# ATtiny10_v2.net
KiCad netlist of a schematic drawn in EAGLE
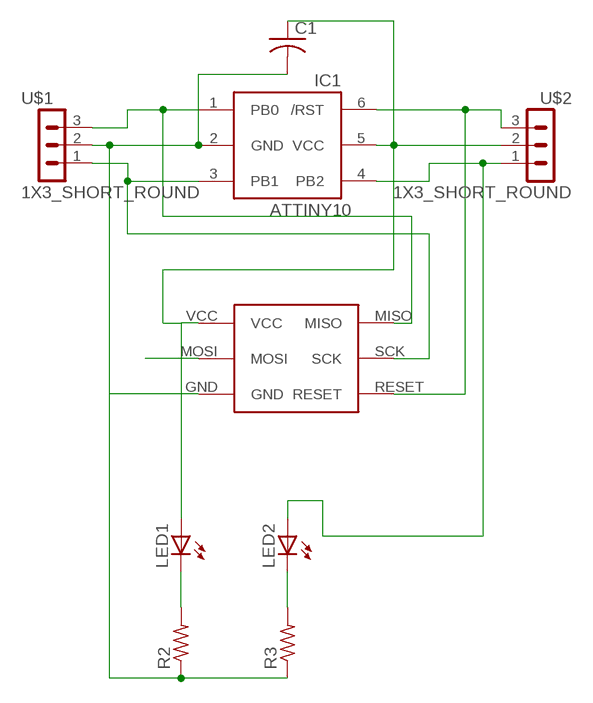
[diagram p0: schematic, sheet 1]

(export (version "E")
  (design (tool "Eeschema 10.0.6"))
  (components
    (comp (ref "C1")
      (value "C-USC0402K")
      (footprint "eagle-import:C0402K")
      (libsource (lib "eagle-import") (part "C-USC0402K"))
    )
    (comp (ref "IC1")
      (value "ATTINY10")
      (footprint "eagle-import:SOT23-6")
      (libsource (lib "eagle-import") (part "ATTINY10"))
    )
    (comp (ref "LED1")
      (value "LEDCHIPLED_0603")
      (footprint "eagle-import:CHIPLED_0603")
      (libsource (lib "eagle-import") (part "LEDCHIPLED_0603"))
    )
    (comp (ref "LED2")
      (value "LEDCHIPLED_0603")
      (footprint "eagle-import:CHIPLED_0603")
      (libsource (lib "eagle-import") (part "LEDCHIPLED_0603"))
    )
    (comp (ref "R2")
      (value "R-US_R0402")
      (footprint "eagle-import:R0402")
      (libsource (lib "eagle-import") (part "R-US_R0402"))
    )
    (comp (ref "R3")
      (value "R-US_R0402")
      (footprint "eagle-import:R0402")
      (libsource (lib "eagle-import") (part "R-US_R0402"))
    )
    (comp (ref "U$1")
      (value "1X3_SHORT_ROUND")
      (footprint "eagle-import:1X3_SHORT_ROUND")
      (libsource (lib "eagle-import") (part "1X3_SHORT_ROUND"))
    )
    (comp (ref "U$2")
      (value "1X3_SHORT_ROUND")
      (footprint "eagle-import:1X3_SHORT_ROUND")
      (libsource (lib "eagle-import") (part "1X3_SHORT_ROUND"))
    )
    (comp (ref "U$4")
      (value "TINY-AVR-POGO-PIN-KEY")
      (footprint "eagle-import:TINY-AVR-POGO-PIN-KEY")
      (libsource (lib "eagle-import") (part "TINY-AVR-POGO-PIN-KEY"))
    )
  )
  (nets
    (net (code "1") (name "Net-(IC1-GND)") (class "Default")
      (node (ref "C1") (pin "2") (pinfunction "2_2") (pintype "passive"))
      (node (ref "IC1") (pin "2") (pinfunction "GND_2") (pintype "power_in"))
      (node (ref "R2") (pin "1") (pinfunction "1_1") (pintype "passive"))
      (node (ref "R3") (pin "1") (pinfunction "1_1") (pintype "passive"))
      (node (ref "U$1") (pin "2") (pinfunction "5_2") (pintype "passive"))
      (node (ref "U$4") (pin "GND") (pinfunction "GND_GND") (pintype "bidirectional"))
    )
    (net (code "2") (name "Net-(IC1-PB0)") (class "Default")
      (node (ref "IC1") (pin "1") (pinfunction "PB0_1") (pintype "bidirectional"))
      (node (ref "U$1") (pin "3") (pinfunction "6_3") (pintype "passive"))
      (node (ref "U$4") (pin "MISO") (pinfunction "MISO_MISO") (pintype "bidirectional"))
    )
    (net (code "3") (name "Net-(IC1-PB1)") (class "Default")
      (node (ref "IC1") (pin "3") (pinfunction "PB1_3") (pintype "bidirectional"))
      (node (ref "U$1") (pin "1") (pinfunction "4_1") (pintype "passive"))
      (node (ref "U$4") (pin "SCK") (pinfunction "SCK_SCK") (pintype "bidirectional"))
    )
    (net (code "4") (name "Net-(IC1-PB2)") (class "Default")
      (node (ref "IC1") (pin "4") (pinfunction "PB2_4") (pintype "bidirectional"))
      (node (ref "LED2") (pin "A") (pinfunction "A_A") (pintype "passive"))
      (node (ref "U$2") (pin "1") (pinfunction "4_1") (pintype "passive"))
    )
    (net (code "5") (name "Net-(IC1-VCC)") (class "Default")
      (node (ref "C1") (pin "1") (pinfunction "1_1") (pintype "passive"))
      (node (ref "IC1") (pin "5") (pinfunction "VCC_5") (pintype "power_in"))
      (node (ref "LED1") (pin "A") (pinfunction "A_A") (pintype "passive"))
      (node (ref "U$2") (pin "2") (pinfunction "5_2") (pintype "passive"))
      (node (ref "U$4") (pin "VCC") (pinfunction "VCC_VCC") (pintype "bidirectional"))
    )
    (net (code "6") (name "Net-(IC1-{slash}RST)") (class "Default")
      (node (ref "IC1") (pin "6") (pinfunction "/RST_6") (pintype "bidirectional"))
      (node (ref "U$2") (pin "3") (pinfunction "6_3") (pintype "passive"))
      (node (ref "U$4") (pin "RESET") (pinfunction "RESET_RESET") (pintype "bidirectional"))
    )
    (net (code "7") (name "Net-(LED1-PadC)") (class "Default")
      (node (ref "LED1") (pin "C") (pinfunction "C_C") (pintype "passive"))
      (node (ref "R2") (pin "2") (pinfunction "2_2") (pintype "passive"))
    )
    (net (code "8") (name "Net-(LED2-PadC)") (class "Default")
      (node (ref "LED2") (pin "C") (pinfunction "C_C") (pintype "passive"))
      (node (ref "R3") (pin "2") (pinfunction "2_2") (pintype "passive"))
    )
    (net (code "9") (name "unconnected-(U$4-PadMOSI)") (class "Default")
      (node (ref "U$4") (pin "MOSI") (pinfunction "MOSI_MOSI") (pintype "bidirectional"))
    )
  )
)
